# SCH_new-gen_2025-10-19.net
KiCad netlist of a schematic drawn in EasyEDA
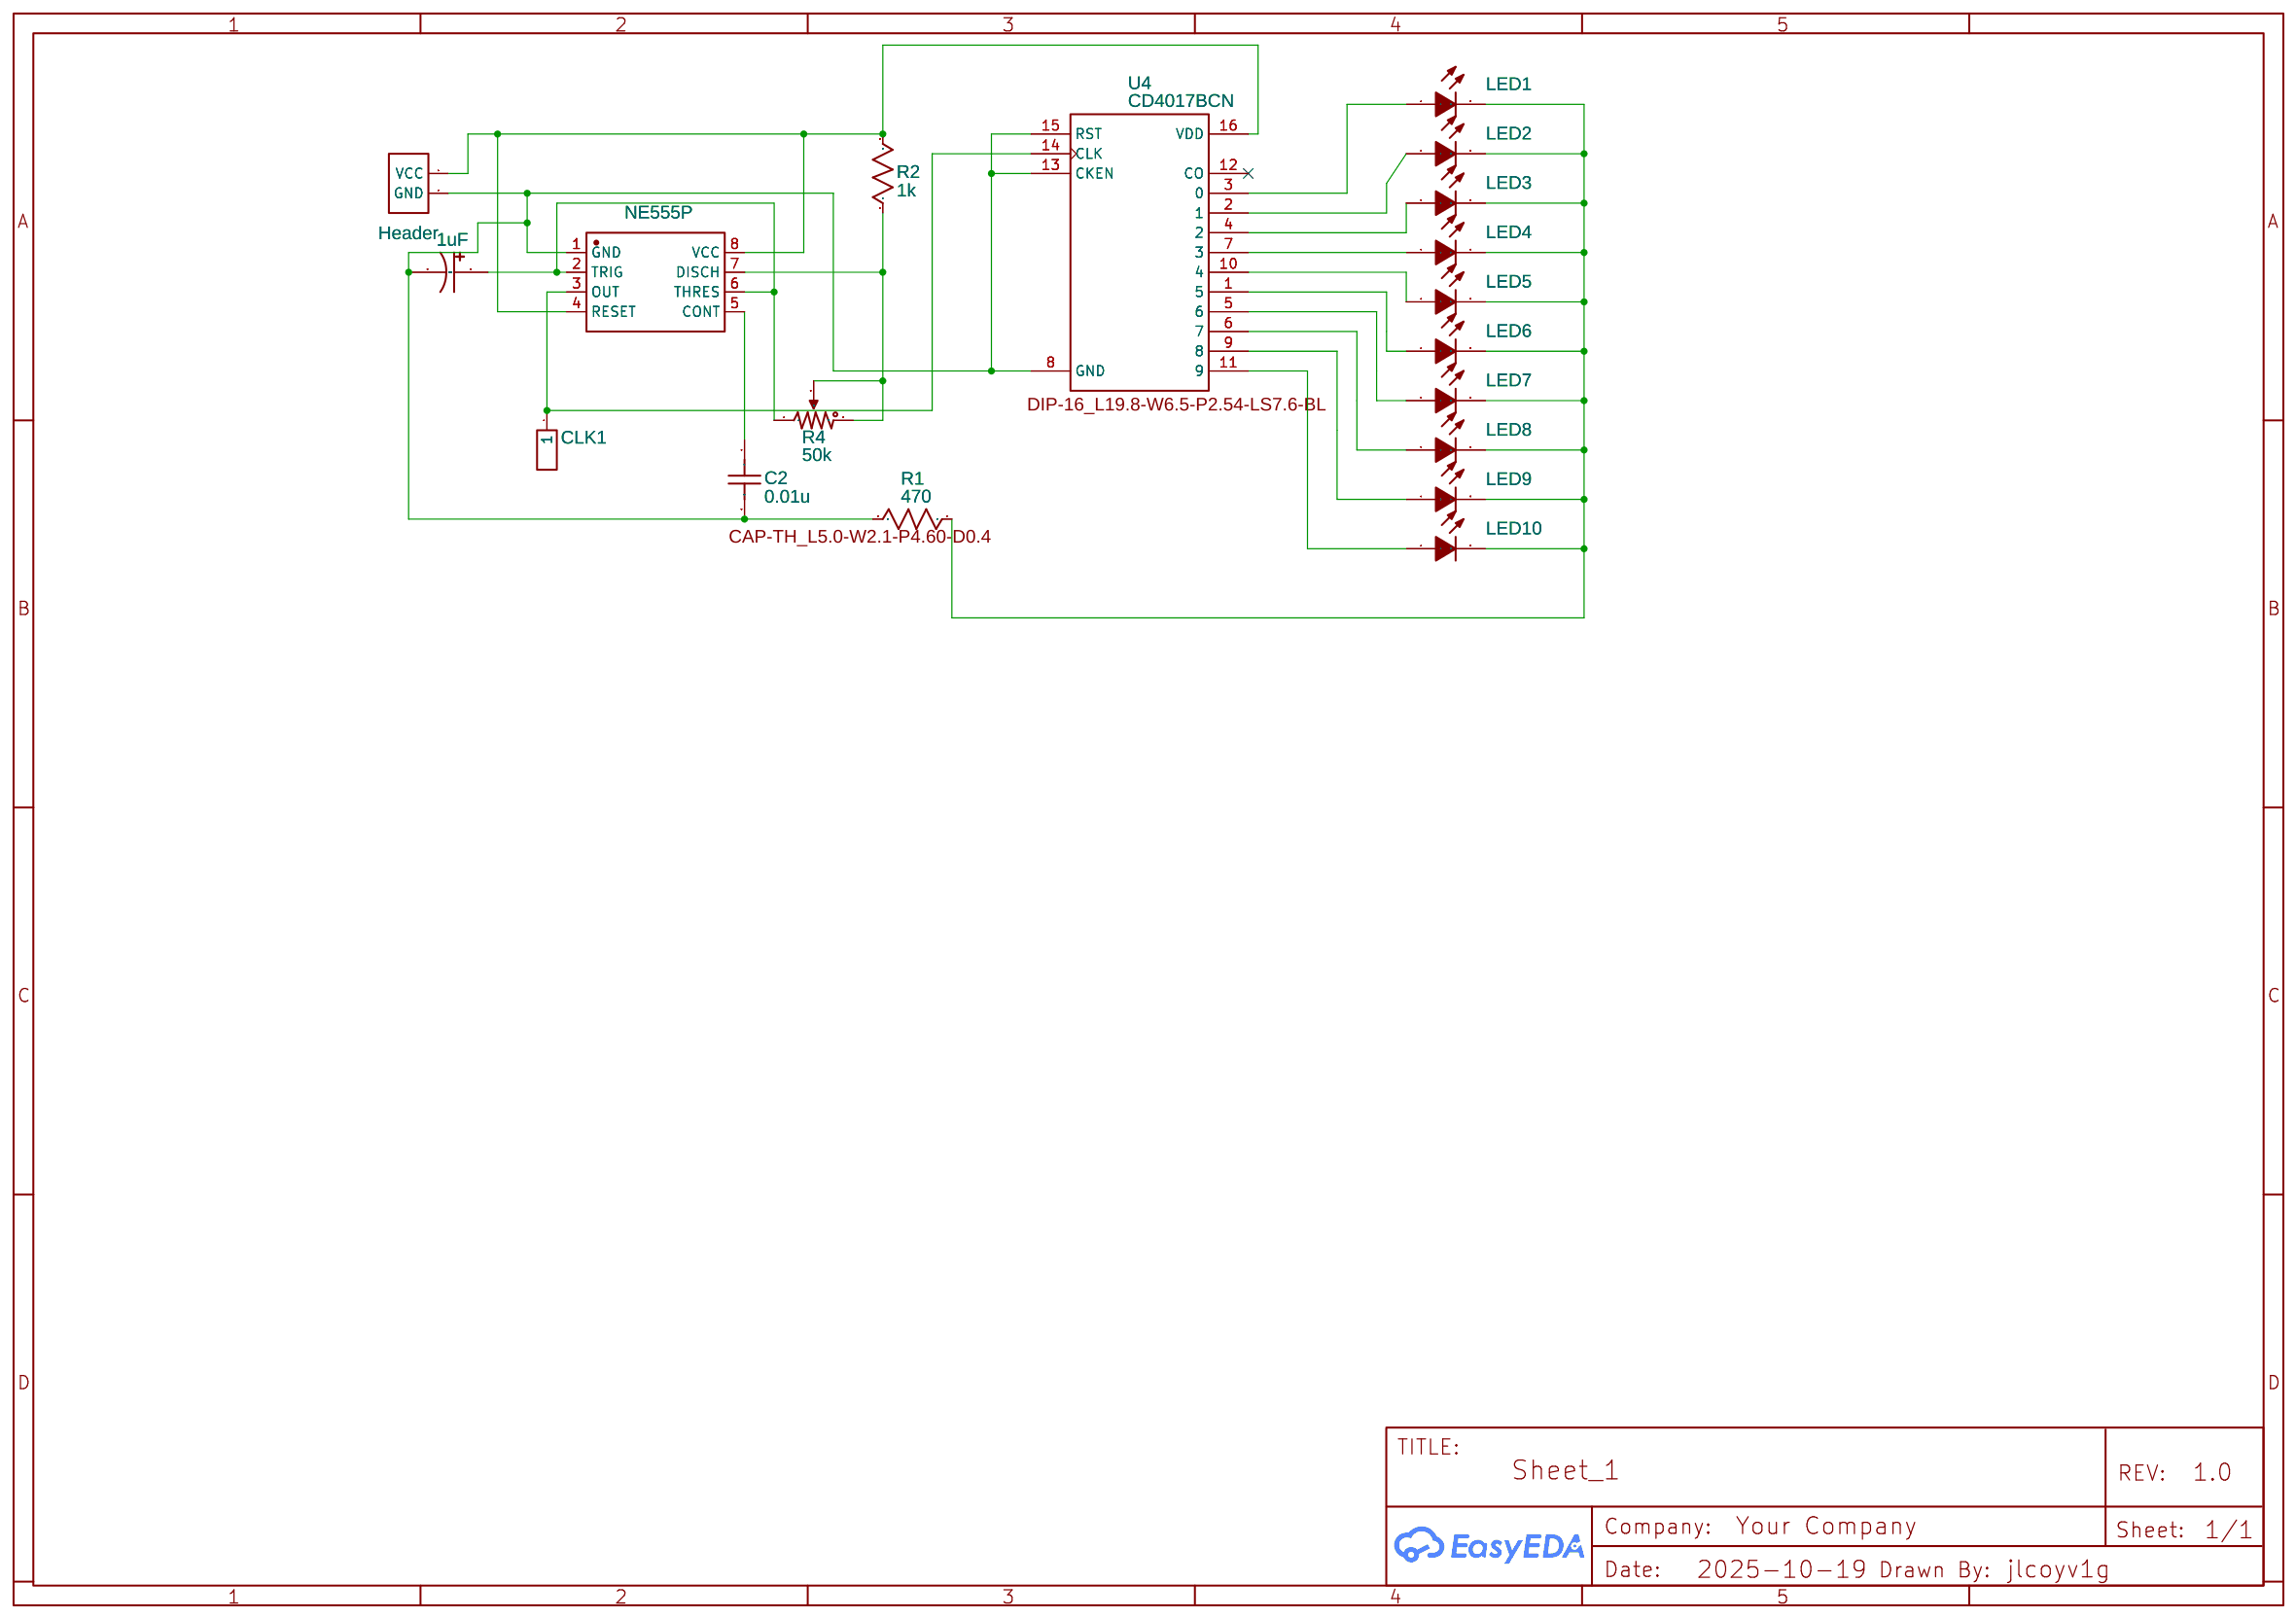
[diagram p0: schematic sheet]

(export (version "E")
  (design (tool "Eeschema 10.0.6"))
  (components
    (comp (ref "C1")
      (value "1uF")
      (fields (field (name "Manufacturer Part") "UVZ1H010MDD") (field (name "Manufacturer") "Nichicon(尼吉康)"))
      (libsource (lib "") (part "UVZ1H010MDD"))
    )
    (comp (ref "C2") (value "0.01u") (libsource (lib "") (part "C_0603_US")))
    (comp (ref "CLK1")
      (value "C81276")
      (fields
        (field (name "Manufacturer Part") "2.54-1*1P针")
        (field (name "Manufacturer") "BOOMELE(Boom Precision Elec)")
      )
      (libsource (lib "") (part "Header-Male-2.54_1x1"))
    )
    (comp (ref "H1") (value "Header") (libsource (lib "") (part "HEADER-FEMALE-2.54_1X2")))
    (comp (ref "LED1") (value "LED_5MM") (libsource (lib "") (part "LED_5MM")))
    (comp (ref "LED2") (value "LED_5MM") (libsource (lib "") (part "LED_5MM")))
    (comp (ref "LED3") (value "LED_5MM") (libsource (lib "") (part "LED_5MM")))
    (comp (ref "LED4") (value "LED_5MM") (libsource (lib "") (part "LED_5MM")))
    (comp (ref "LED5") (value "LED_5MM") (libsource (lib "") (part "LED_5MM")))
    (comp (ref "LED6") (value "LED_5MM") (libsource (lib "") (part "LED_5MM")))
    (comp (ref "LED7") (value "LED_5MM") (libsource (lib "") (part "LED_5MM")))
    (comp (ref "LED8") (value "LED_5MM") (libsource (lib "") (part "LED_5MM")))
    (comp (ref "LED9") (value "LED_5MM") (libsource (lib "") (part "LED_5MM")))
    (comp (ref "LED10") (value "LED_5MM") (libsource (lib "") (part "LED_5MM")))
    (comp (ref "R1")
      (value "470")
      (fields (field (name "Manufacturer Part") "?"))
      (libsource (lib "") (part "Resistor_1"))
    )
    (comp (ref "R2")
      (value "1k")
      (fields (field (name "Manufacturer Part") "?"))
      (libsource (lib "") (part "Resistor"))
    )
    (comp (ref "R4")
      (value "50k")
      (fields (field (name "Manufacturer Part") "?"))
      (libsource (lib "") (part "Potentiometer"))
    )
    (comp (ref "U2")
      (value "NE555P")
      (fields (field (name "Manufacturer") "TI(德州仪器)"))
      (libsource (lib "") (part "NE555P"))
    )
    (comp (ref "U4") (value "CD4017BCN") (libsource (lib "") (part "CD4017BCN")))
  )
  (nets
    (net (code "1") (name "Net-(H1-GND)") (class "Default")
      (node (ref "C1") (pin "2") (pinfunction "2_2") (pintype "unspecified"))
      (node (ref "C2") (pin "2") (pinfunction "2_2") (pintype "unspecified"))
      (node (ref "H1") (pin "2") (pinfunction "GND_2") (pintype "unspecified"))
      (node (ref "R1") (pin "2") (pinfunction "2_2") (pintype "unspecified"))
      (node (ref "U2") (pin "1") (pinfunction "GND_1") (pintype "unspecified"))
      (node (ref "U4") (pin "13") (pinfunction "CKEN_13") (pintype "unspecified"))
      (node (ref "U4") (pin "15") (pinfunction "RST_15") (pintype "unspecified"))
      (node (ref "U4") (pin "8") (pinfunction "GND_8") (pintype "passive"))
    )
    (net (code "2") (name "Net-(H1-VCC)") (class "Default")
      (node (ref "H1") (pin "1") (pinfunction "VCC_1") (pintype "unspecified"))
      (node (ref "R2") (pin "2") (pinfunction "2_2") (pintype "unspecified"))
      (node (ref "U2") (pin "4") (pinfunction "RESET_4") (pintype "unspecified"))
      (node (ref "U2") (pin "8") (pinfunction "VCC_8") (pintype "unspecified"))
      (node (ref "U4") (pin "16") (pinfunction "VDD_16") (pintype "passive"))
    )
    (net (code "3") (name "Net-(LED1-A)") (class "Default")
      (node (ref "LED1") (pin "1") (pinfunction "A_1") (pintype "input"))
      (node (ref "U4") (pin "3") (pinfunction "0_3") (pintype "output"))
    )
    (net (code "4") (name "Net-(LED1-K)") (class "Default")
      (node (ref "LED1") (pin "2") (pinfunction "K_2") (pintype "input"))
      (node (ref "LED10") (pin "2") (pinfunction "K_2") (pintype "input"))
      (node (ref "LED2") (pin "2") (pinfunction "K_2") (pintype "input"))
      (node (ref "LED3") (pin "2") (pinfunction "K_2") (pintype "input"))
      (node (ref "LED4") (pin "2") (pinfunction "K_2") (pintype "input"))
      (node (ref "LED5") (pin "2") (pinfunction "K_2") (pintype "input"))
      (node (ref "LED6") (pin "2") (pinfunction "K_2") (pintype "input"))
      (node (ref "LED7") (pin "2") (pinfunction "K_2") (pintype "input"))
      (node (ref "LED8") (pin "2") (pinfunction "K_2") (pintype "input"))
      (node (ref "LED9") (pin "2") (pinfunction "K_2") (pintype "input"))
      (node (ref "R1") (pin "1") (pinfunction "1_1") (pintype "unspecified"))
    )
    (net (code "5") (name "Net-(LED2-A)") (class "Default")
      (node (ref "LED2") (pin "1") (pinfunction "A_1") (pintype "input"))
      (node (ref "U4") (pin "2") (pinfunction "1_2") (pintype "output"))
    )
    (net (code "6") (name "Net-(LED3-A)") (class "Default")
      (node (ref "LED3") (pin "1") (pinfunction "A_1") (pintype "input"))
      (node (ref "U4") (pin "4") (pinfunction "2_4") (pintype "output"))
    )
    (net (code "7") (name "Net-(LED4-A)") (class "Default")
      (node (ref "LED4") (pin "1") (pinfunction "A_1") (pintype "input"))
      (node (ref "U4") (pin "7") (pinfunction "3_7") (pintype "output"))
    )
    (net (code "8") (name "Net-(LED5-A)") (class "Default")
      (node (ref "LED5") (pin "1") (pinfunction "A_1") (pintype "input"))
      (node (ref "U4") (pin "10") (pinfunction "4_10") (pintype "output"))
    )
    (net (code "9") (name "Net-(LED6-A)") (class "Default")
      (node (ref "LED6") (pin "1") (pinfunction "A_1") (pintype "input"))
      (node (ref "U4") (pin "1") (pinfunction "5_1") (pintype "output"))
    )
    (net (code "10") (name "Net-(LED7-A)") (class "Default")
      (node (ref "LED7") (pin "1") (pinfunction "A_1") (pintype "input"))
      (node (ref "U4") (pin "5") (pinfunction "6_5") (pintype "output"))
    )
    (net (code "11") (name "Net-(LED8-A)") (class "Default")
      (node (ref "LED8") (pin "1") (pinfunction "A_1") (pintype "input"))
      (node (ref "U4") (pin "6") (pinfunction "7_6") (pintype "output"))
    )
    (net (code "12") (name "Net-(LED9-A)") (class "Default")
      (node (ref "LED9") (pin "1") (pinfunction "A_1") (pintype "input"))
      (node (ref "U4") (pin "9") (pinfunction "8_9") (pintype "output"))
    )
    (net (code "13") (name "Net-(LED10-A)") (class "Default")
      (node (ref "LED10") (pin "1") (pinfunction "A_1") (pintype "input"))
      (node (ref "U4") (pin "11") (pinfunction "9_11") (pintype "output"))
    )
    (net (code "14") (name "Net-(R4-2)") (class "Default")
      (node (ref "R2") (pin "1") (pinfunction "1_1") (pintype "unspecified"))
      (node (ref "R4") (pin "2") (pinfunction "3_2") (pintype "unspecified"))
      (node (ref "R4") (pin "3") (pinfunction "2_3") (pintype "unspecified"))
      (node (ref "U2") (pin "7") (pinfunction "DISCH_7") (pintype "unspecified"))
    )
    (net (code "15") (name "Net-(U2-CONT)") (class "Default")
      (node (ref "C2") (pin "1") (pinfunction "1_1") (pintype "unspecified"))
      (node (ref "U2") (pin "5") (pinfunction "CONT_5") (pintype "unspecified"))
    )
    (net (code "16") (name "Net-(U2-OUT)") (class "Default")
      (node (ref "CLK1") (pin "1") (pinfunction "1_1") (pintype "unspecified"))
      (node (ref "U2") (pin "3") (pinfunction "OUT_3") (pintype "unspecified"))
      (node (ref "U4") (pin "14") (pinfunction "CLK_14") (pintype "unspecified"))
    )
    (net (code "17") (name "Net-(U2-THRES)") (class "Default")
      (node (ref "C1") (pin "1") (pinfunction "1_1") (pintype "unspecified"))
      (node (ref "R4") (pin "1") (pinfunction "1_1") (pintype "unspecified"))
      (node (ref "U2") (pin "2") (pinfunction "TRIG_2") (pintype "unspecified"))
      (node (ref "U2") (pin "6") (pinfunction "THRES_6") (pintype "unspecified"))
    )
    (net (code "18") (name "unconnected-(U4-CO-Pad12)") (class "Default")
      (node (ref "U4") (pin "12") (pinfunction "CO_12") (pintype "output+no_connect"))
    )
  )
)
